# resistor_test_2.net
KiCad netlist of a schematic drawn in EAGLE
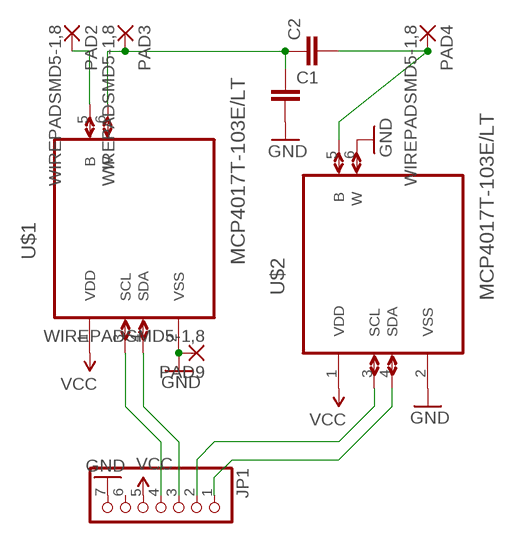
[diagram p0: schematic, sheet 1]

(export (version "E")
  (design (tool "Eeschema 10.0.6"))
  (components
    (comp (ref "C1")
      (value "C-EUC0603")
      (footprint "eagle-import:C0603")
      (libsource (lib "eagle-import") (part "C-EUC0603"))
    )
    (comp (ref "C2")
      (value "C-EUC0603")
      (footprint "eagle-import:C0603")
      (libsource (lib "eagle-import") (part "C-EUC0603"))
    )
    (comp (ref "JP1")
      (value "PINHD-1X7")
      (footprint "eagle-import:1X07")
      (libsource (lib "eagle-import") (part "PINHD-1X7"))
    )
    (comp (ref "PAD2")
      (value "WIREPADSMD5-1,8")
      (footprint "eagle-import:5-1,8")
      (libsource (lib "eagle-import") (part "WIREPADSMD5-1,8"))
    )
    (comp (ref "PAD3")
      (value "WIREPADSMD5-1,8")
      (footprint "eagle-import:5-1,8")
      (libsource (lib "eagle-import") (part "WIREPADSMD5-1,8"))
    )
    (comp (ref "PAD4")
      (value "WIREPADSMD5-1,8")
      (footprint "eagle-import:5-1,8")
      (libsource (lib "eagle-import") (part "WIREPADSMD5-1,8"))
    )
    (comp (ref "PAD9")
      (value "WIREPADSMD5-1,8")
      (footprint "eagle-import:5-1,8")
      (libsource (lib "eagle-import") (part "WIREPADSMD5-1,8"))
    )
    (comp (ref "U$1")
      (value "MCP4017T-103E/LT")
      (footprint "eagle-import:SOT65P210X110-6N")
      (fields (field (name "MF") "Microchip"))
      (libsource (lib "eagle-import") (part "MCP4017T-103E/LT"))
    )
    (comp (ref "U$2")
      (value "MCP4017T-103E/LT")
      (footprint "eagle-import:SOT65P210X110-6N")
      (fields (field (name "MF") "Microchip"))
      (libsource (lib "eagle-import") (part "MCP4017T-103E/LT"))
    )
  )
  (nets
    (net (code "1") (name "GND") (class "Default")
      (node (ref "C1") (pin "2") (pinfunction "2_2") (pintype "passive"))
      (node (ref "JP1") (pin "7") (pinfunction "7_7") (pintype "passive"))
      (node (ref "PAD9") (pin "1") (pinfunction "P_1") (pintype "passive"))
      (node (ref "U$1") (pin "2") (pinfunction "VSS_2") (pintype "power_in"))
      (node (ref "U$2") (pin "2") (pinfunction "VSS_2") (pintype "power_in"))
      (node (ref "U$2") (pin "6") (pinfunction "W_6") (pintype "bidirectional"))
    )
    (net (code "2") (name "Net-(PAD2-P)") (class "Default")
      (node (ref "PAD2") (pin "1") (pinfunction "P_1") (pintype "passive"))
      (node (ref "U$1") (pin "5") (pinfunction "B_5") (pintype "bidirectional"))
    )
    (net (code "3") (name "Net-(PAD3-P)") (class "Default")
      (node (ref "C1") (pin "1") (pinfunction "1_1") (pintype "passive"))
      (node (ref "C2") (pin "1") (pinfunction "1_1") (pintype "passive"))
      (node (ref "PAD3") (pin "1") (pinfunction "P_1") (pintype "passive"))
      (node (ref "U$1") (pin "6") (pinfunction "W_6") (pintype "bidirectional"))
    )
    (net (code "4") (name "Net-(PAD4-P)") (class "Default")
      (node (ref "C2") (pin "2") (pinfunction "2_2") (pintype "passive"))
      (node (ref "PAD4") (pin "1") (pinfunction "P_1") (pintype "passive"))
      (node (ref "U$2") (pin "5") (pinfunction "B_5") (pintype "bidirectional"))
    )
    (net (code "5") (name "Net-(U$1-SCL)") (class "Default")
      (node (ref "JP1") (pin "4") (pinfunction "4_4") (pintype "passive"))
      (node (ref "U$1") (pin "3") (pinfunction "SCL_3") (pintype "bidirectional"))
    )
    (net (code "6") (name "Net-(U$1-SDA)") (class "Default")
      (node (ref "JP1") (pin "3") (pinfunction "3_3") (pintype "passive"))
      (node (ref "U$1") (pin "4") (pinfunction "SDA_4") (pintype "bidirectional"))
    )
    (net (code "7") (name "Net-(U$2-SCL)") (class "Default")
      (node (ref "JP1") (pin "2") (pinfunction "2_2") (pintype "passive"))
      (node (ref "U$2") (pin "3") (pinfunction "SCL_3") (pintype "bidirectional"))
    )
    (net (code "8") (name "Net-(U$2-SDA)") (class "Default")
      (node (ref "JP1") (pin "1") (pinfunction "1_1") (pintype "passive"))
      (node (ref "U$2") (pin "4") (pinfunction "SDA_4") (pintype "bidirectional"))
    )
    (net (code "9") (name "VCC") (class "Default")
      (node (ref "JP1") (pin "5") (pinfunction "5_5") (pintype "passive"))
      (node (ref "U$1") (pin "1") (pinfunction "VDD_1") (pintype "power_in"))
      (node (ref "U$2") (pin "1") (pinfunction "VDD_1") (pintype "power_in"))
    )
    (net (code "10") (name "unconnected-(JP1-Pad6)") (class "Default")
      (node (ref "JP1") (pin "6") (pinfunction "6_6") (pintype "passive"))
    )
  )
)
